# samd21.net
KiCad netlist of a schematic drawn in Altium Designer
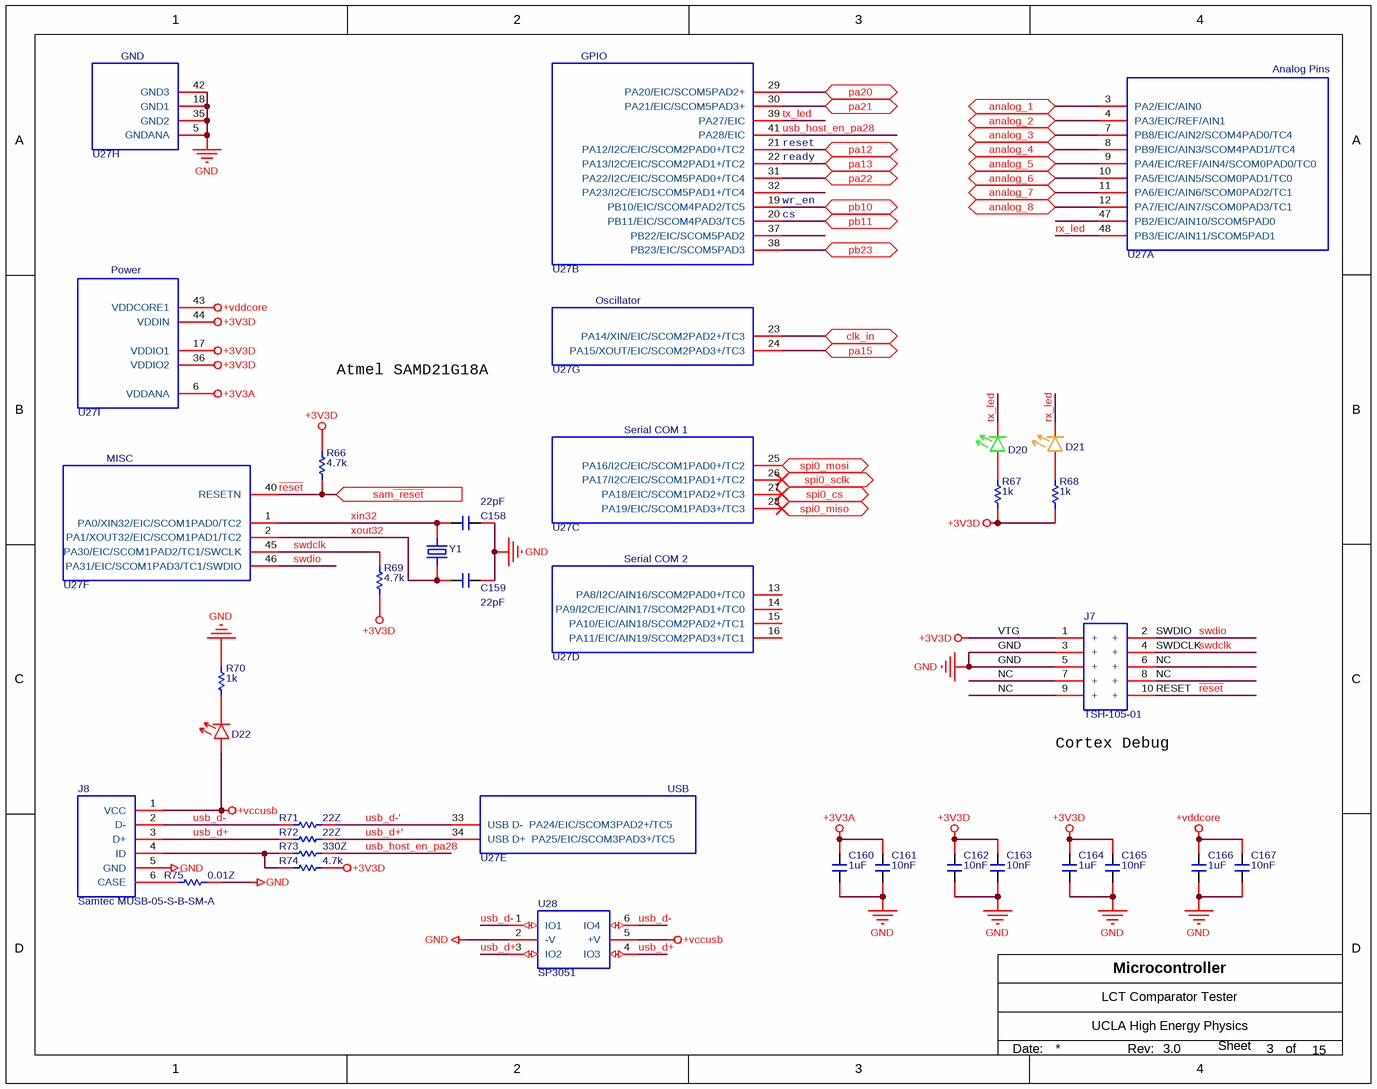
[diagram p0: samd21.SchDoc]

(export (version "E")
  (design (tool "Eeschema 10.0.6"))
  (components
    (comp (ref "C158")
      (value "22pF")
      (footprint "C0603")
      (description "CAP-CER, 0, 22pF, 10%, 100V, 0603, NP0")
      (fields
        (field (name "MANUFACTURER") "Kemet")
        (field (name "MANUFACTURER PART NUMBER") "C0603C220J1GACTU")
      )
      (libsource (lib "stdlib") (part "CAP/C0603C220J1GACTU"))
    )
    (comp (ref "C159")
      (value "22pF")
      (footprint "C0603")
      (description "CAP-CER, 0, 22pF, 10%, 100V, 0603, NP0")
      (fields
        (field (name "MANUFACTURER") "Kemet")
        (field (name "MANUFACTURER PART NUMBER") "C0603C220J1GACTU")
      )
      (libsource (lib "stdlib") (part "CAP/C0603C220J1GACTU"))
    )
    (comp (ref "C160")
      (value "1uF")
      (footprint "C0603")
      (description "CAP-CER, 2, 1.0uF, 10%, 25V, 0603")
      (fields
        (field (name "MANUFACTURER") "Murata Electronics North America")
        (field (name "MANUFACTURER PART NUMBER") "GRM188R61E105KA12D")
      )
      (libsource (lib "stdlib") (part "Murata/GRM188R61E105KA12D"))
    )
    (comp (ref "C161")
      (value "10nF")
      (footprint "C0603")
      (description "CAP-CER, 2, 0.01uF, 10%, 50V, X7R, 0603")
      (fields
        (field (name "MANUFACTURER") "Murata Electronics North America")
        (field (name "MANUFACTURER PART NUMBER") "GRM188R71H103KA01D")
      )
      (libsource (lib "stdlib") (part "CAP/GRM188R71H103KA01D"))
    )
    (comp (ref "C162")
      (value "10nF")
      (footprint "C0603")
      (description "CAP-CER, 2, 0.01uF, 10%, 50V, X7R, 0603")
      (fields
        (field (name "MANUFACTURER") "Murata Electronics North America")
        (field (name "MANUFACTURER PART NUMBER") "GRM188R71H103KA01D")
      )
      (libsource (lib "stdlib") (part "CAP/GRM188R71H103KA01D"))
    )
    (comp (ref "C163")
      (value "10nF")
      (footprint "C0603")
      (description "CAP-CER, 2, 0.01uF, 10%, 50V, X7R, 0603")
      (fields
        (field (name "MANUFACTURER") "Murata Electronics North America")
        (field (name "MANUFACTURER PART NUMBER") "GRM188R71H103KA01D")
      )
      (libsource (lib "stdlib") (part "CAP/GRM188R71H103KA01D"))
    )
    (comp (ref "C164")
      (value "1uF")
      (footprint "C0603")
      (description "CAP-CER, 2, 1.0uF, 10%, 25V, 0603")
      (fields
        (field (name "MANUFACTURER") "Murata Electronics North America")
        (field (name "MANUFACTURER PART NUMBER") "GRM188R61E105KA12D")
      )
      (libsource (lib "stdlib") (part "Murata/GRM188R61E105KA12D"))
    )
    (comp (ref "C165")
      (value "10nF")
      (footprint "C0603")
      (description "CAP-CER, 2, 0.01uF, 10%, 50V, X7R, 0603")
      (fields
        (field (name "MANUFACTURER") "Murata Electronics North America")
        (field (name "MANUFACTURER PART NUMBER") "GRM188R71H103KA01D")
      )
      (libsource (lib "stdlib") (part "CAP/GRM188R71H103KA01D"))
    )
    (comp (ref "C166")
      (value "1uF")
      (footprint "C0603")
      (description "CAP-CER, 2, 1.0uF, 10%, 25V, 0603")
      (fields
        (field (name "MANUFACTURER") "Murata Electronics North America")
        (field (name "MANUFACTURER PART NUMBER") "GRM188R61E105KA12D")
      )
      (libsource (lib "stdlib") (part "Murata/GRM188R61E105KA12D"))
    )
    (comp (ref "C167")
      (value "10nF")
      (footprint "C0603")
      (description "CAP-CER, 2, 0.01uF, 10%, 50V, X7R, 0603")
      (fields
        (field (name "MANUFACTURER") "Murata Electronics North America")
        (field (name "MANUFACTURER PART NUMBER") "GRM188R71H103KA01D")
      )
      (libsource (lib "stdlib") (part "CAP/GRM188R71H103KA01D"))
    )
    (comp (ref "D20")
      (value "LITEON/LTST-C191KGKT")
      (footprint "LED0603")
      (description "LED, 20mA, 0603, Green")
      (libsource (lib "stdlib") (part "LITEON/LTST-C191KGKT"))
    )
    (comp (ref "D21")
      (value "Vishay/TLMO1000-GS08")
      (footprint "LED0603")
      (description "LED, 2mA, 0603, Soft Orange")
      (fields
        (field (name "MANUFACTURER") "Vishay Semiconductor Opto Division")
        (field (name "MANUFACTURER PART NUMBER") "TLMO1000-GS08")
      )
      (libsource (lib "stdlib") (part "Vishay/TLMO1000-GS08"))
    )
    (comp (ref "D22")
      (value "Vishay/TLMS1000-GS08")
      (footprint "LED0603")
      (description "LED, 2mA, 0603, Red")
      (fields
        (field (name "MANUFACTURER") "Vishay Semiconductor Opto Division")
        (field (name "MANUFACTURER PART NUMBER") "TLMS1000-GS08")
      )
      (libsource (lib "stdlib") (part "Vishay/TLMS1000-GS08"))
    )
    (comp (ref "J7")
      (value "TSH-105-01")
      (footprint "Samtec/FTSH-105-XX-XXX-DV-A")
      (description "Header, 1.27mm, 02x05")
      (fields
        (field (name "MANUFACTURER") "Samtec Inc.")
        (field (name "MANUFACTURER PART NUMBER") "FTSH-105-01-F-DV-K")
      )
      (libsource (lib "stdlib") (part "Samtec/TSH-105-01"))
    )
    (comp (ref "J8")
      (value "Samtec MUSB-05-S-B-SM-A")
      (footprint "MUSB-05-S-B-SM-A")
      (description "USB, Mini-USB, SMD")
      (fields
        (field (name "MANUFACTURER") "Samtec Inc.")
        (field (name "MANUFACTURER PART NUMBER") "MUSB-05-S-B-SM-A")
      )
      (libsource (lib "stdlib") (part "Samtec/MUSB-05-S-B-SM-A"))
    )
    (comp (ref "R66")
      (value "4.7k")
      (footprint "R0603")
      (description "RES1, SMD, 4.70k, 1.0%, 1/10W, 0603")
      (fields
        (field (name "MANUFACTURER") "Vishay Dale")
        (field (name "MANUFACTURER PART NUMBER") "CRCW06034K70FKEA")
      )
      (libsource (lib "stdlib") (part "CRCW06034K70FKEA"))
    )
    (comp (ref "R67")
      (value "1k")
      (footprint "R0603")
      (description "RES1, SMD, 1.00k, 1.0%, 1/10W, 0603")
      (fields
        (field (name "MANUFACTURER") "Vishay Dale")
        (field (name "MANUFACTURER PART NUMBER") "CRCW06031K00FKEA")
      )
      (libsource (lib "stdlib") (part "CRCW06031K00FKEA"))
    )
    (comp (ref "R68")
      (value "1k")
      (footprint "R0603")
      (description "RES1, SMD, 1.00k, 1.0%, 1/10W, 0603")
      (fields
        (field (name "MANUFACTURER") "Vishay Dale")
        (field (name "MANUFACTURER PART NUMBER") "CRCW06031K00FKEA")
      )
      (libsource (lib "stdlib") (part "CRCW06031K00FKEA"))
    )
    (comp (ref "R69")
      (value "4.7k")
      (footprint "R0603")
      (description "RES1, SMD, 4.70k, 1.0%, 1/10W, 0603")
      (fields
        (field (name "MANUFACTURER") "Vishay Dale")
        (field (name "MANUFACTURER PART NUMBER") "CRCW06034K70FKEA")
      )
      (libsource (lib "stdlib") (part "CRCW06034K70FKEA"))
    )
    (comp (ref "R70")
      (value "1k")
      (footprint "R0603")
      (description "RES1, SMD, 1.00k, 1.0%, 1/10W, 0603")
      (fields
        (field (name "MANUFACTURER") "Vishay Dale")
        (field (name "MANUFACTURER PART NUMBER") "CRCW06031K00FKEA")
      )
      (libsource (lib "stdlib") (part "CRCW06031K00FKEA"))
    )
    (comp (ref "R71")
      (value "22Z")
      (footprint "R0402")
      (description "RES0, SMD, 22.0Z, 1.0%, 1/16W, 0402")
      (fields
        (field (name "MANUFACTURER") "Yageo")
        (field (name "MANUFACTURER PART NUMBER") "RC0402FR-0722RL")
      )
      (libsource (lib "stdlib") (part "RES/ 311-22.0LRCT-ND"))
    )
    (comp (ref "R72")
      (value "22Z")
      (footprint "R0402")
      (description "RES0, SMD, 22.0Z, 1.0%, 1/16W, 0402")
      (fields
        (field (name "MANUFACTURER") "Yageo")
        (field (name "MANUFACTURER PART NUMBER") "RC0402FR-0722RL")
      )
      (libsource (lib "stdlib") (part "RES/ 311-22.0LRCT-ND"))
    )
    (comp (ref "R73")
      (value "330Z")
      (footprint "R0603")
      (description "RES0, SMD,  330Z, 1.0%, 1/10W, 0603")
      (fields
        (field (name "MANUFACTURER") "Rohm Semiconductor")
        (field (name "MANUFACTURER PART NUMBER") "MCR03ERTF3300")
      )
      (libsource (lib "stdlib") (part "CRCW0603330RFKEA"))
    )
    (comp (ref "R74")
      (value "4.7k")
      (footprint "R0603")
      (description "RES1, SMD, 4.70k, 1.0%, 1/10W, 0603")
      (fields
        (field (name "MANUFACTURER") "Vishay Dale")
        (field (name "MANUFACTURER PART NUMBER") "CRCW06034K70FKEA")
      )
      (libsource (lib "stdlib") (part "CRCW06034K70FKEA"))
    )
    (comp (ref "R75")
      (value "0.01Z")
      (footprint "R1206")
      (description "RES0, SMD, 0.01Z, 1.0%, 1/4W,  1206")
      (fields
        (field (name "MANUFACTURER") "Panasonic Electronic Components")
        (field (name "MANUFACTURER PART NUMBER") "ERJ-8BWFR010V")
      )
      (libsource (lib "stdlib") (part "RES SMD 0.01 OHM 1% 1W 1206"))
    )
    (comp (ref "U27")
      (value "SAMD21G18A-AUT")
      (footprint "TSQFP50P900X900X120-48N")
      (description "Atmel D21 32bit ARM Cortex-M0  microcontroller - 48 PIN TQFP 256KB flash memory + 32KB SRAM")
      (fields
        (field (name "MANUFACTURER") "Atmel")
        (field (name "MANUFACTURER PART NUMBER") "ATSAMD21G18A-AUT")
      )
      (libsource (lib "stdlib") (part "Atmel/SAMD21G18A"))
    )
    (comp (ref "U28")
      (value "SP3051")
      (footprint "SOT23-6")
      (description "TVS, 6VWM, 16VC")
      (fields
        (field (name "MANUFACTURER") "Littelfuse Inc.")
        (field (name "MANUFACTURER PART NUMBER") "SP3051-04HTG")
      )
      (libsource (lib "stdlib") (part "Littelfuse/SP3051-04HTG"))
    )
    (comp (ref "Y1")
      (value "32.768 kHz")
      (footprint "ABRACON ABS07")
      (description "XTAL, 32.768 kHz, 12.5pF, SMD")
      (fields
        (field (name "MANUFACTURER") "Abracon LLC")
        (field (name "MANUFACTURER PART NUMBER") "ABS07-32.768KHZ-T")
      )
      (libsource (lib "stdlib") (part "Abracon/ABS07-32.768KHZ-T"))
    )
  )
  (nets
    (net (code "1") (name "+3V3A") (class "Default")
      (node (ref "C160") (pin "2") (pinfunction "2_2") (pintype "passive"))
      (node (ref "C161") (pin "1") (pinfunction "5_1") (pintype "passive"))
      (node (ref "U27") (pin "6") (pinfunction "VDDANA_6") (pintype "power_in"))
    )
    (net (code "2") (name "+3V3D") (class "Default")
      (node (ref "C162") (pin "2") (pinfunction "2_2") (pintype "passive"))
      (node (ref "C163") (pin "1") (pinfunction "5_1") (pintype "passive"))
      (node (ref "C164") (pin "1") (pinfunction "5_1") (pintype "passive"))
      (node (ref "C165") (pin "1") (pinfunction "5_1") (pintype "passive"))
      (node (ref "J7") (pin "1") (pinfunction "+_1") (pintype "passive"))
      (node (ref "R66") (pin "2") (pinfunction "2_2") (pintype "passive"))
      (node (ref "R67") (pin "1") (pinfunction "1_1") (pintype "passive"))
      (node (ref "R68") (pin "1") (pinfunction "1_1") (pintype "passive"))
      (node (ref "R69") (pin "1") (pinfunction "1_1") (pintype "passive"))
      (node (ref "R74") (pin "2") (pinfunction "2_2") (pintype "passive"))
      (node (ref "U27") (pin "17") (pinfunction "VDDIO1_17") (pintype "power_in"))
      (node (ref "U27") (pin "36") (pinfunction "VDDIO2_36") (pintype "power_in"))
      (node (ref "U27") (pin "44") (pinfunction "VDDIN_44") (pintype "power_in"))
    )
    (net (code "3") (name "+vccusb") (class "Default")
      (node (ref "D22") (pin "A") (pintype "passive"))
      (node (ref "J8") (pin "1") (pinfunction "VCC_1") (pintype "passive"))
      (node (ref "U28") (pin "5") (pinfunction "+V_5") (pintype "power_in"))
    )
    (net (code "4") (name "+vddcore") (class "Default")
      (node (ref "C166") (pin "1") (pinfunction "5_1") (pintype "passive"))
      (node (ref "C167") (pin "1") (pinfunction "5_1") (pintype "passive"))
      (node (ref "U27") (pin "43") (pinfunction "VDDCORE1_43") (pintype "passive"))
    )
    (net (code "5") (name "/analog_1") (class "Default")
      (node (ref "U27") (pin "3") (pinfunction "PA2/EIC/AIN0_3") (pintype "passive"))
    )
    (net (code "6") (name "/analog_2") (class "Default")
      (node (ref "U27") (pin "4") (pinfunction "PA3/EIC/REF/AIN1_4") (pintype "passive"))
    )
    (net (code "7") (name "/analog_3") (class "Default")
      (node (ref "U27") (pin "7") (pinfunction "PB8/EIC/AIN2/SCOM4PAD0/TC4_7") (pintype "passive"))
    )
    (net (code "8") (name "/analog_4") (class "Default")
      (node (ref "U27") (pin "8") (pinfunction "PB9/EIC/AIN3/SCOM4PAD1//TC4_8") (pintype "passive"))
    )
    (net (code "9") (name "/analog_5") (class "Default")
      (node (ref "U27") (pin "9") (pinfunction "PA4/EIC/REF/AIN4/SCOM0PAD0/TC0_9") (pintype "passive"))
    )
    (net (code "10") (name "/analog_6") (class "Default")
      (node (ref "U27") (pin "10") (pinfunction "PA5/EIC/AIN5/SCOM0PAD1/TC0_10") (pintype "passive"))
    )
    (net (code "11") (name "/analog_7") (class "Default")
      (node (ref "U27") (pin "11") (pinfunction "PA6/EIC/AIN6/SCOM0PAD2/TC1_11") (pintype "passive"))
    )
    (net (code "12") (name "/analog_8") (class "Default")
      (node (ref "U27") (pin "12") (pinfunction "PA7/EIC/AIN7/SCOM0PAD3/TC1_12") (pintype "passive"))
    )
    (net (code "13") (name "/clk_in") (class "Default")
      (node (ref "U27") (pin "23") (pinfunction "PA14/XIN/EIC/SCOM2PAD2+/TC3_23") (pintype "passive"))
    )
    (net (code "14") (name "/pa12") (class "Default")
      (node (ref "U27") (pin "21") (pinfunction "PA12/I2C/EIC/SCOM2PAD0+/TC2_21") (pintype "passive"))
    )
    (net (code "15") (name "/pa13") (class "Default")
      (node (ref "U27") (pin "22") (pinfunction "PA13/I2C/EIC/SCOM2PAD1+/TC2_22") (pintype "passive"))
    )
    (net (code "16") (name "/pa15") (class "Default")
      (node (ref "U27") (pin "24") (pinfunction "PA15/XOUT/EIC/SCOM2PAD3+/TC3_24") (pintype "passive"))
    )
    (net (code "17") (name "/pa20") (class "Default")
      (node (ref "U27") (pin "29") (pinfunction "PA20/EIC/SCOM5PAD2+_29") (pintype "passive"))
    )
    (net (code "18") (name "/pa21") (class "Default")
      (node (ref "U27") (pin "30") (pinfunction "PA21/EIC/SCOM5PAD3+_30") (pintype "passive"))
    )
    (net (code "19") (name "/pa22") (class "Default")
      (node (ref "U27") (pin "31") (pinfunction "PA22/I2C/EIC/SCOM5PAD0+/TC4_31") (pintype "passive"))
    )
    (net (code "20") (name "/pb10") (class "Default")
      (node (ref "U27") (pin "19") (pinfunction "PB10/EIC/SCOM4PAD2/TC5_19") (pintype "passive"))
    )
    (net (code "21") (name "/pb11") (class "Default")
      (node (ref "U27") (pin "20") (pinfunction "PB11/EIC/SCOM4PAD3/TC5_20") (pintype "passive"))
    )
    (net (code "22") (name "/pb23") (class "Default")
      (node (ref "U27") (pin "38") (pinfunction "PB23/EIC/SCOM5PAD3_38") (pintype "passive"))
    )
    (net (code "23") (name "/reset") (class "Default")
      (node (ref "J7") (pin "10") (pinfunction "+_10") (pintype "passive"))
      (node (ref "R66") (pin "1") (pinfunction "1_1") (pintype "passive"))
      (node (ref "U27") (pin "40") (pinfunction "RESETN_40") (pintype "passive"))
    )
    (net (code "24") (name "/rx_led") (class "Default")
      (node (ref "D21") (pin "C") (pintype "passive"))
      (node (ref "U27") (pin "48") (pinfunction "PB3/EIC/AIN11/SCOM5PAD1_48") (pintype "passive"))
    )
    (net (code "25") (name "/spi0_cs") (class "Default")
      (node (ref "U27") (pin "27") (pinfunction "PA18/EIC/SCOM1PAD2+/TC3_27") (pintype "passive+no_connect"))
    )
    (net (code "26") (name "/spi0_miso") (class "Default")
      (node (ref "U27") (pin "28") (pinfunction "PA19/EIC/SCOM1PAD3+/TC3_28") (pintype "passive+no_connect"))
    )
    (net (code "27") (name "/spi0_mosi") (class "Default")
      (node (ref "U27") (pin "25") (pinfunction "PA16/I2C/EIC/SCOM1PAD0+/TC2_25") (pintype "passive"))
    )
    (net (code "28") (name "/spi0_sclk") (class "Default")
      (node (ref "U27") (pin "26") (pinfunction "PA17/I2C/EIC/SCOM1PAD1+/TC2_26") (pintype "passive+no_connect"))
    )
    (net (code "29") (name "/swdclk") (class "Default")
      (node (ref "J7") (pin "4") (pinfunction "+_4") (pintype "passive"))
      (node (ref "R69") (pin "2") (pinfunction "2_2") (pintype "passive"))
      (node (ref "U27") (pin "45") (pinfunction "PA30/EIC/SCOM1PAD2/TC1/SWCLK_45") (pintype "passive"))
    )
    (net (code "30") (name "/swdio") (class "Default")
      (node (ref "J7") (pin "2") (pinfunction "+_2") (pintype "passive"))
      (node (ref "U27") (pin "46") (pinfunction "PA31/EIC/SCOM1PAD3/TC1/SWDIO_46") (pintype "passive"))
    )
    (net (code "31") (name "/tx_led") (class "Default")
      (node (ref "D20") (pin "C") (pintype "passive"))
      (node (ref "U27") (pin "39") (pinfunction "PA27/EIC_39") (pintype "passive"))
    )
    (net (code "32") (name "/usb_d+") (class "Default")
      (node (ref "J8") (pin "3") (pinfunction "D+_3") (pintype "passive"))
      (node (ref "R72") (pin "1") (pinfunction "1_1") (pintype "passive"))
      (node (ref "U28") (pin "3") (pinfunction "IO2_3") (pintype "bidirectional"))
      (node (ref "U28") (pin "4") (pinfunction "IO3_4") (pintype "bidirectional"))
    )
    (net (code "33") (name "/usb_d+'") (class "Default")
      (node (ref "R72") (pin "2") (pinfunction "2_2") (pintype "passive"))
      (node (ref "U27") (pin "34") (pinfunction "USB_D+__PA25/EIC/SCOM3PAD3+/TC5_34") (pintype "passive"))
    )
    (net (code "34") (name "/usb_d-") (class "Default")
      (node (ref "J8") (pin "2") (pinfunction "D-_2") (pintype "passive"))
      (node (ref "R71") (pin "1") (pinfunction "1_1") (pintype "passive"))
      (node (ref "U28") (pin "1") (pinfunction "IO1_1") (pintype "bidirectional"))
      (node (ref "U28") (pin "6") (pinfunction "IO4_6") (pintype "bidirectional"))
    )
    (net (code "35") (name "/usb_d-'") (class "Default")
      (node (ref "R71") (pin "2") (pinfunction "2_2") (pintype "passive"))
      (node (ref "U27") (pin "33") (pinfunction "USB_D-__PA24/EIC/SCOM3PAD2+/TC5_33") (pintype "passive"))
    )
    (net (code "36") (name "/usb_host_en_pa28") (class "Default")
      (node (ref "R73") (pin "2") (pinfunction "2_2") (pintype "passive"))
      (node (ref "U27") (pin "41") (pinfunction "PA28/EIC_41") (pintype "passive"))
    )
    (net (code "37") (name "/xin32") (class "Default")
      (node (ref "C158") (pin "1") (pinfunction "5_1") (pintype "passive"))
      (node (ref "U27") (pin "1") (pinfunction "PA0/XIN32/EIC/SCOM1PAD0/TC2_1") (pintype "passive"))
      (node (ref "Y1") (pin "2") (pinfunction "2_2") (pintype "passive"))
    )
    (net (code "38") (name "/xout32") (class "Default")
      (node (ref "C159") (pin "1") (pinfunction "5_1") (pintype "passive"))
      (node (ref "U27") (pin "2") (pinfunction "PA1/XOUT32/EIC/SCOM1PAD1/TC2_2") (pintype "passive"))
      (node (ref "Y1") (pin "1") (pinfunction "1_1") (pintype "passive"))
    )
    (net (code "39") (name "GND") (class "Default")
      (node (ref "C158") (pin "2") (pinfunction "2_2") (pintype "passive"))
      (node (ref "C159") (pin "2") (pinfunction "2_2") (pintype "passive"))
      (node (ref "C160") (pin "1") (pinfunction "5_1") (pintype "passive"))
      (node (ref "C161") (pin "2") (pinfunction "2_2") (pintype "passive"))
      (node (ref "C162") (pin "1") (pinfunction "5_1") (pintype "passive"))
      (node (ref "C163") (pin "2") (pinfunction "2_2") (pintype "passive"))
      (node (ref "C164") (pin "2") (pinfunction "2_2") (pintype "passive"))
      (node (ref "C165") (pin "2") (pinfunction "2_2") (pintype "passive"))
      (node (ref "C166") (pin "2") (pinfunction "2_2") (pintype "passive"))
      (node (ref "C167") (pin "2") (pinfunction "2_2") (pintype "passive"))
      (node (ref "J7") (pin "3") (pinfunction "+_3") (pintype "passive"))
      (node (ref "J7") (pin "5") (pinfunction "+_5") (pintype "passive"))
      (node (ref "J8") (pin "5") (pinfunction "GND_5") (pintype "passive"))
      (node (ref "R70") (pin "1") (pinfunction "1_1") (pintype "passive"))
      (node (ref "R75") (pin "2") (pinfunction "2_2") (pintype "passive"))
      (node (ref "U27") (pin "18") (pinfunction "GND1_18") (pintype "power_in"))
      (node (ref "U27") (pin "35") (pinfunction "GND2_35") (pintype "power_in"))
      (node (ref "U27") (pin "42") (pinfunction "GND3_42") (pintype "power_in"))
      (node (ref "U27") (pin "5") (pinfunction "GNDANA_5") (pintype "power_in"))
      (node (ref "U28") (pin "2") (pinfunction "-V_2") (pintype "power_in"))
    )
    (net (code "40") (name "Net-(D20-PadA)") (class "Default")
      (node (ref "D20") (pin "A") (pintype "passive"))
      (node (ref "R67") (pin "2") (pinfunction "2_2") (pintype "passive"))
    )
    (net (code "41") (name "Net-(D21-PadA)") (class "Default")
      (node (ref "D21") (pin "A") (pintype "passive"))
      (node (ref "R68") (pin "2") (pinfunction "2_2") (pintype "passive"))
    )
    (net (code "42") (name "Net-(D22-PadC)") (class "Default")
      (node (ref "D22") (pin "C") (pintype "passive"))
      (node (ref "R70") (pin "2") (pinfunction "2_2") (pintype "passive"))
    )
    (net (code "43") (name "Net-(J8-CASE)") (class "Default")
      (node (ref "J8") (pin "6") (pinfunction "CASE_6") (pintype "passive"))
      (node (ref "R75") (pin "1") (pinfunction "1_1") (pintype "passive"))
    )
    (net (code "44") (name "Net-(J8-ID)") (class "Default")
      (node (ref "J8") (pin "4") (pinfunction "ID_4") (pintype "passive"))
      (node (ref "R73") (pin "1") (pinfunction "1_1") (pintype "passive"))
      (node (ref "R74") (pin "1") (pinfunction "1_1") (pintype "passive"))
    )
    (net (code "45") (name "unconnected-(J7-+-Pad6)") (class "Default")
      (node (ref "J7") (pin "6") (pinfunction "+_6") (pintype "passive"))
    )
    (net (code "46") (name "unconnected-(J7-+-Pad7)") (class "Default")
      (node (ref "J7") (pin "7") (pinfunction "+_7") (pintype "passive"))
    )
    (net (code "47") (name "unconnected-(J7-+-Pad8)") (class "Default")
      (node (ref "J7") (pin "8") (pinfunction "+_8") (pintype "passive"))
    )
    (net (code "48") (name "unconnected-(J7-+-Pad9)") (class "Default")
      (node (ref "J7") (pin "9") (pinfunction "+_9") (pintype "passive"))
    )
    (net (code "49") (name "unconnected-(U27A-PB2{slash}EIC{slash}AIN10{slash}SCOM5PAD0-Pad47)") (class "Default")
      (node (ref "U27") (pin "47") (pinfunction "PB2/EIC/AIN10/SCOM5PAD0_47") (pintype "passive"))
    )
    (net (code "50") (name "unconnected-(U27B-PA23{slash}I2C{slash}EIC{slash}SCOM5PAD1+{slash}TC4-Pad32)") (class "Default")
      (node (ref "U27") (pin "32") (pinfunction "PA23/I2C/EIC/SCOM5PAD1+/TC4_32") (pintype "passive"))
    )
    (net (code "51") (name "unconnected-(U27B-PB22{slash}EIC{slash}SCOM5PAD2-Pad37)") (class "Default")
      (node (ref "U27") (pin "37") (pinfunction "PB22/EIC/SCOM5PAD2_37") (pintype "passive"))
    )
    (net (code "52") (name "unconnected-(U27D-PA8{slash}I2C{slash}AIN16{slash}SCOM2PAD0+{slash}TC0-Pad13)") (class "Default")
      (node (ref "U27") (pin "13") (pinfunction "PA8/I2C/AIN16/SCOM2PAD0+/TC0_13") (pintype "passive"))
    )
    (net (code "53") (name "unconnected-(U27D-PA9{slash}I2C{slash}EIC{slash}AIN17{slash}SCOM2PAD1+{slash}TC0-Pad14)") (class "Default")
      (node (ref "U27") (pin "14") (pinfunction "PA9/I2C/EIC/AIN17/SCOM2PAD1+/TC0_14") (pintype "passive"))
    )
    (net (code "54") (name "unconnected-(U27D-PA10{slash}EIC{slash}AIN18{slash}SCOM2PAD2+{slash}TC1-Pad15)") (class "Default")
      (node (ref "U27") (pin "15") (pinfunction "PA10/EIC/AIN18/SCOM2PAD2+/TC1_15") (pintype "passive"))
    )
    (net (code "55") (name "unconnected-(U27D-PA11{slash}EIC{slash}AIN19{slash}SCOM2PAD3+{slash}TC1-Pad16)") (class "Default")
      (node (ref "U27") (pin "16") (pinfunction "PA11/EIC/AIN19/SCOM2PAD3+/TC1_16") (pintype "passive"))
    )
  )
)
